# ariton_alexandru_fin.net
KiCad netlist of a schematic drawn in EAGLE
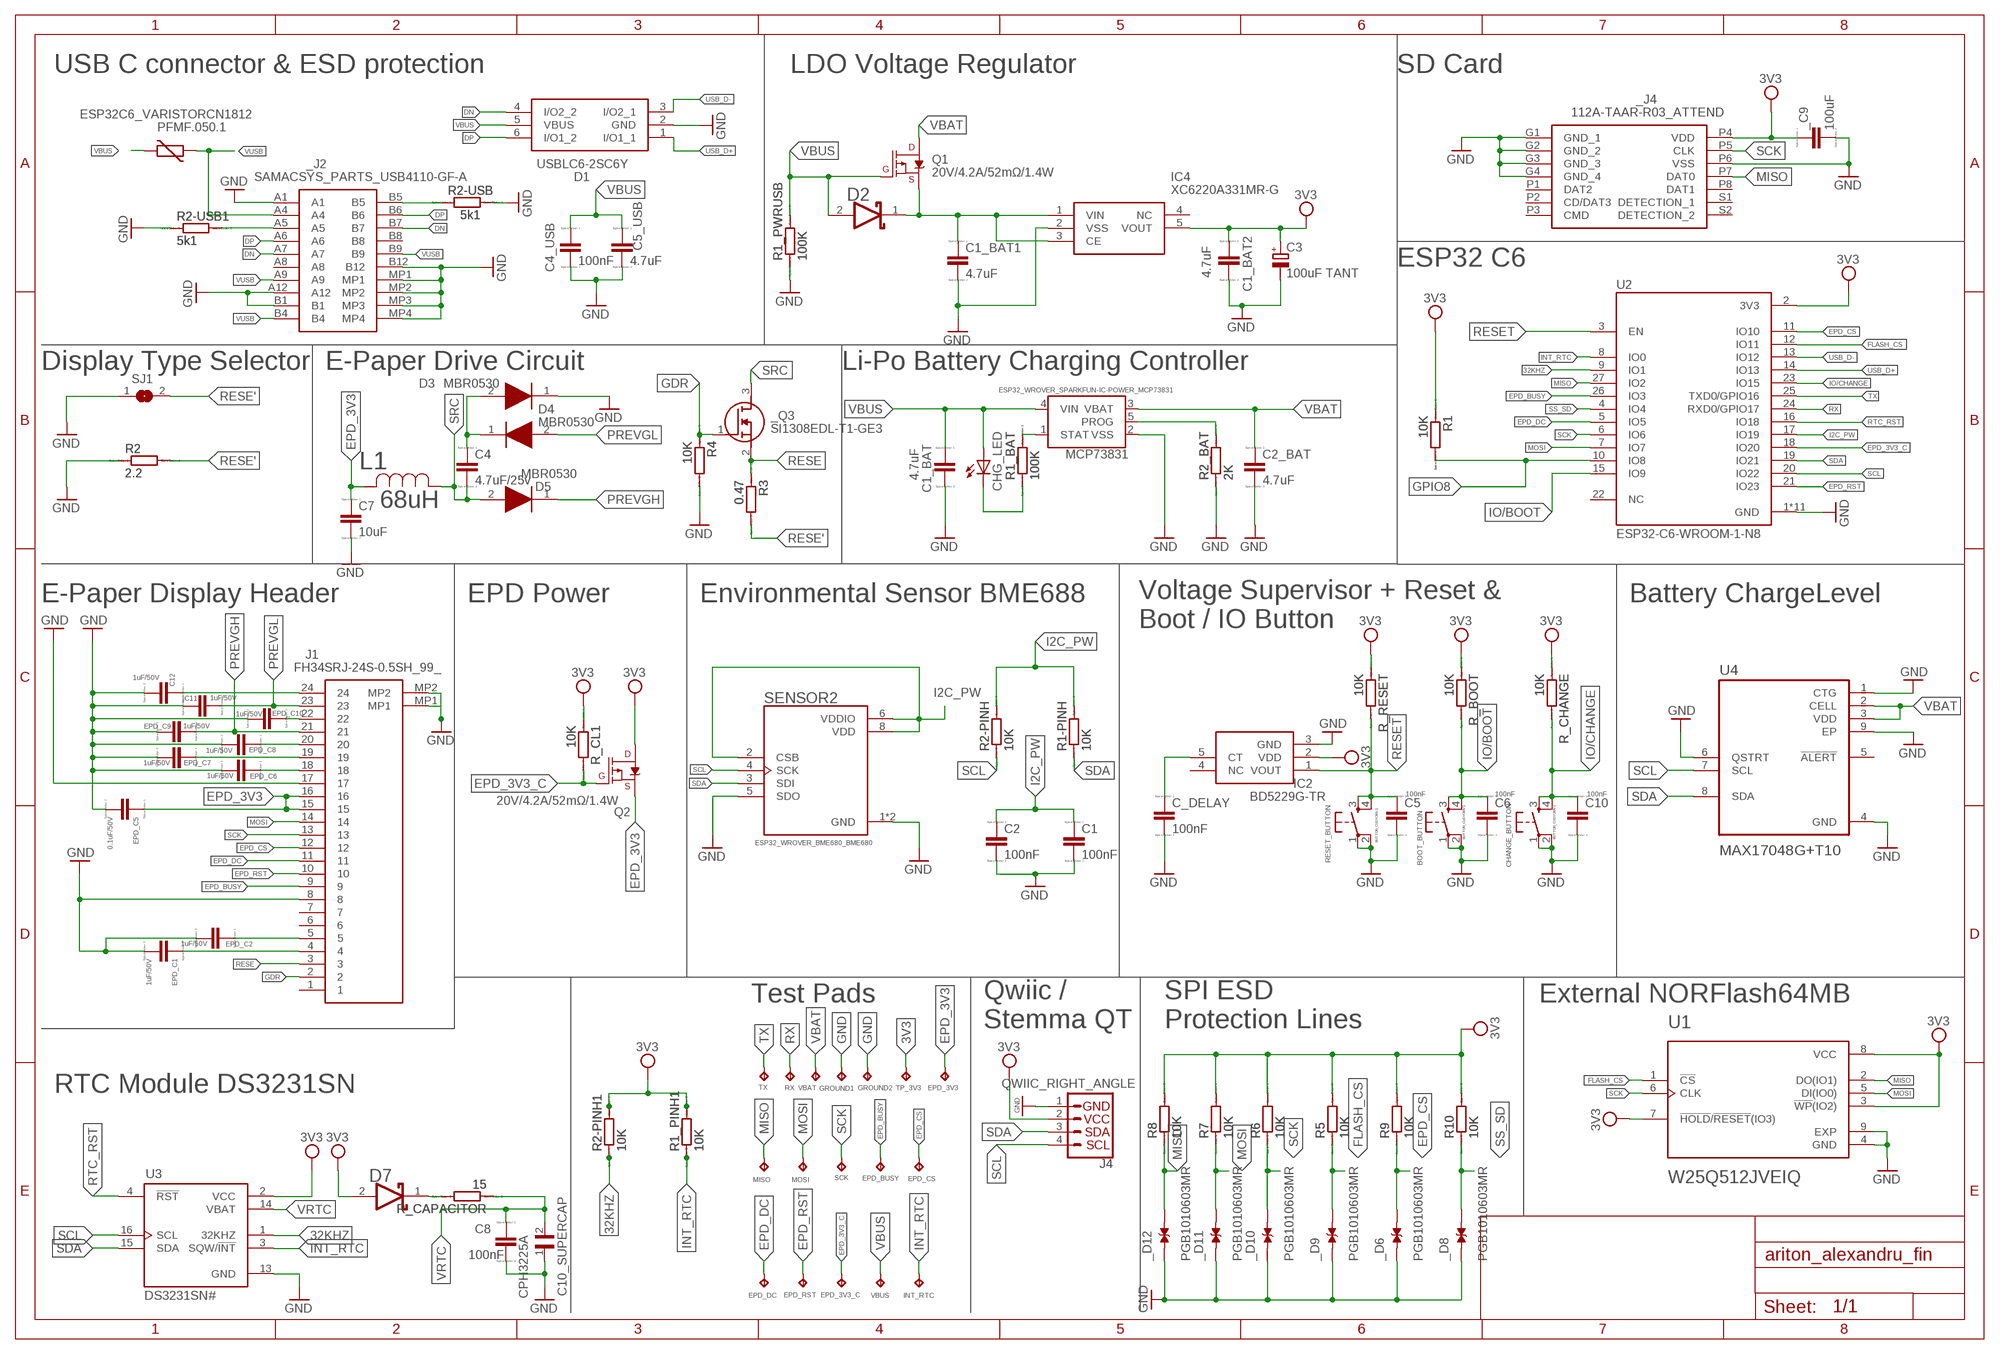
[diagram p0: schematic, sheet 1]

(export (version "E")
  (design (tool "Eeschema 10.0.6"))
  (components
    (comp (ref "BOOT_BUTTON")
      (value "BUTTON_CUSYOMV1")
      (footprint "eagle-import:MYBUTTON")
      (libsource (lib "eagle-import") (part "BUTTON_CUSYOMV1"))
    )
    (comp (ref "C1")
      (value "100nF")
      (footprint "eagle-import:EAGLE-LTSPICE_C0402")
      (libsource (lib "eagle-import") (part "EAGLE-LTSPICE_CC0402"))
    )
    (comp (ref "C1_BAT")
      (value "4.7uF")
      (footprint "eagle-import:EAGLE-LTSPICE_C0402")
      (libsource (lib "eagle-import") (part "EAGLE-LTSPICE_CC0402"))
    )
    (comp (ref "C1_BAT1")
      (value "4.7uF")
      (footprint "eagle-import:EAGLE-LTSPICE_C0402")
      (libsource (lib "eagle-import") (part "EAGLE-LTSPICE_CC0402"))
    )
    (comp (ref "C1_BAT2")
      (value "4.7uF")
      (footprint "eagle-import:EAGLE-LTSPICE_C0402")
      (libsource (lib "eagle-import") (part "EAGLE-LTSPICE_CC0402"))
    )
    (comp (ref "C2")
      (value "100nF")
      (footprint "eagle-import:EAGLE-LTSPICE_C0402")
      (libsource (lib "eagle-import") (part "EAGLE-LTSPICE_CC0402"))
    )
    (comp (ref "C2_BAT")
      (value "4.7uF")
      (footprint "eagle-import:EAGLE-LTSPICE_C0402")
      (libsource (lib "eagle-import") (part "EAGLE-LTSPICE_CC0402"))
    )
    (comp (ref "C3")
      (value "100uF TANT")
      (footprint "eagle-import:RCL_CT3528")
      (libsource (lib "eagle-import") (part "RCL_CPOL-EUCT3528"))
    )
    (comp (ref "C4")
      (value "4.7uF/25v")
      (footprint "eagle-import:EAGLE-LTSPICE_C0402")
      (libsource (lib "eagle-import") (part "EAGLE-LTSPICE_CC0402"))
    )
    (comp (ref "C4_USB")
      (value "100nF")
      (footprint "eagle-import:EAGLE-LTSPICE_C0402")
      (libsource (lib "eagle-import") (part "EAGLE-LTSPICE_CC0402"))
    )
    (comp (ref "C5")
      (value "100nF")
      (footprint "eagle-import:ESP32_WROVER_EAGLE-LTSPICE_C0402")
      (libsource (lib "eagle-import") (part "ESP32_WROVER_EAGLE-LTSPICE_CC0402"))
    )
    (comp (ref "C5_USB")
      (value "4.7uF")
      (footprint "eagle-import:EAGLE-LTSPICE_C0402")
      (libsource (lib "eagle-import") (part "EAGLE-LTSPICE_CC0402"))
    )
    (comp (ref "C6")
      (value "100nF")
      (footprint "eagle-import:ESP32_WROVER_EAGLE-LTSPICE_C0402")
      (libsource (lib "eagle-import") (part "ESP32_WROVER_EAGLE-LTSPICE_CC0402"))
    )
    (comp (ref "C7")
      (value "10uF")
      (footprint "eagle-import:EAGLE-LTSPICE_C0402")
      (libsource (lib "eagle-import") (part "EAGLE-LTSPICE_CC0402"))
    )
    (comp (ref "C8")
      (value "100nF")
      (footprint "eagle-import:EAGLE-LTSPICE_C0402")
      (libsource (lib "eagle-import") (part "EAGLE-LTSPICE_CC0402"))
    )
    (comp (ref "C10")
      (value "100nF")
      (footprint "eagle-import:ESP32_WROVER_EAGLE-LTSPICE_C0402")
      (libsource (lib "eagle-import") (part "ESP32_WROVER_EAGLE-LTSPICE_CC0402"))
    )
    (comp (ref "C10_SUPERCAP")
      (value "CPH3225A")
      (footprint "eagle-import:CAPCP3225X100N")
      (fields (field (name "MF") "Seiko Instruments"))
      (libsource (lib "eagle-import") (part "CPH3225A"))
    )
    (comp (ref "C11")
      (value "1uF/50V")
      (footprint "eagle-import:EAGLE-LTSPICE_C0402")
      (libsource (lib "eagle-import") (part "EAGLE-LTSPICE_CC0402"))
    )
    (comp (ref "C12")
      (value "1uF/50V")
      (footprint "eagle-import:EAGLE-LTSPICE_C0402")
      (libsource (lib "eagle-import") (part "EAGLE-LTSPICE_CC0402"))
    )
    (comp (ref "CHANGE_BUTTON")
      (value "BUTTON_CUSYOMV1")
      (footprint "eagle-import:MYBUTTON")
      (libsource (lib "eagle-import") (part "BUTTON_CUSYOMV1"))
    )
    (comp (ref "CHG_LED")
      (value "ADAFRUIT_LEDCHIP-LED0603")
      (footprint "eagle-import:ADAFRUIT_CHIP-LED0603")
      (libsource (lib "eagle-import") (part "ADAFRUIT_LEDCHIP-LED0603"))
    )
    (comp (ref "C_DELAY")
      (value "100nF")
      (footprint "eagle-import:ESP32_WROVER_EAGLE-LTSPICE_C0402")
      (libsource (lib "eagle-import") (part "ESP32_WROVER_EAGLE-LTSPICE_CC0402"))
    )
    (comp (ref "D1")
      (value "USBLC6-2SC6Y")
      (footprint "eagle-import:SOT95P280X145-6N")
      (fields (field (name "MF") "STMicroelectronics"))
      (libsource (lib "eagle-import") (part "USBLC6-2SC6Y"))
    )
    (comp (ref "D2")
      (value "ESP32_WROVER_AVX---SD0805S020S1R0_AVX_SD0805S020S1R0_0_0AVX_SD0805S020S1R0_0_0")
      (footprint "eagle-import:ESP32_WROVER_AVX---SD0805S020S1R0_AVX_SD0805S020S1R0_0")
      (fields
        (field (name "DIGIKEY_PART_NUMBER") "478-7800-1-ND")
        (field (name "MF") "AVX")
        (field (name "MOUSER_PART_NUMBER") "581-SD0805S020S1R0")
      )
      (libsource (lib "eagle-import") (part "ESP32_WROVER_AVX---SD0805S020S1R0_AVX_SD0805S020S1R0_0_0AVX_SD0805S020S1R0_0_0"))
    )
    (comp (ref "D3")
      (value "MBR0530")
      (footprint "eagle-import:SOD3716X135N")
      (fields (field (name "MF") "ON Semiconductor"))
      (libsource (lib "eagle-import") (part "MBR0530"))
    )
    (comp (ref "D4")
      (value "MBR0530")
      (footprint "eagle-import:SOD3716X135N")
      (fields (field (name "MF") "ON Semiconductor"))
      (libsource (lib "eagle-import") (part "MBR0530"))
    )
    (comp (ref "D5")
      (value "MBR0530")
      (footprint "eagle-import:SOD3716X135N")
      (fields (field (name "MF") "ON Semiconductor"))
      (libsource (lib "eagle-import") (part "MBR0530"))
    )
    (comp (ref "D7")
      (value "ESP32_WROVER_AVX---SD0805S020S1R0_AVX_SD0805S020S1R0_0_0AVX_SD0805S020S1R0_0_0")
      (footprint "eagle-import:ESP32_WROVER_AVX---SD0805S020S1R0_AVX_SD0805S020S1R0_0")
      (fields
        (field (name "DIGIKEY_PART_NUMBER") "478-7800-1-ND")
        (field (name "MF") "AVX")
        (field (name "MOUSER_PART_NUMBER") "581-SD0805S020S1R0")
      )
      (libsource (lib "eagle-import") (part "ESP32_WROVER_AVX---SD0805S020S1R0_AVX_SD0805S020S1R0_0_0AVX_SD0805S020S1R0_0_0"))
    )
    (comp (ref "EPD_3V3")
      (value "TPTP20R")
      (footprint "eagle-import:TP20R")
      (libsource (lib "eagle-import") (part "TPTP20R"))
    )
    (comp (ref "EPD_3V3_C")
      (value "TPTP20R")
      (footprint "eagle-import:TP20R")
      (libsource (lib "eagle-import") (part "TPTP20R"))
    )
    (comp (ref "EPD_BUSY")
      (value "TPTP20R")
      (footprint "eagle-import:TP20R")
      (libsource (lib "eagle-import") (part "TPTP20R"))
    )
    (comp (ref "EPD_C1")
      (value "1uF/50V")
      (footprint "eagle-import:EAGLE-LTSPICE_C0402")
      (libsource (lib "eagle-import") (part "EAGLE-LTSPICE_CC0402"))
    )
    (comp (ref "EPD_C2")
      (value "1uF/50V")
      (footprint "eagle-import:EAGLE-LTSPICE_C0402")
      (libsource (lib "eagle-import") (part "EAGLE-LTSPICE_CC0402"))
    )
    (comp (ref "EPD_C5")
      (value "0.1uF/50V")
      (footprint "eagle-import:EAGLE-LTSPICE_C0402")
      (libsource (lib "eagle-import") (part "EAGLE-LTSPICE_CC0402"))
    )
    (comp (ref "EPD_C6")
      (value "1uF/50V")
      (footprint "eagle-import:EAGLE-LTSPICE_C0402")
      (libsource (lib "eagle-import") (part "EAGLE-LTSPICE_CC0402"))
    )
    (comp (ref "EPD_C7")
      (value "1uF/50V")
      (footprint "eagle-import:EAGLE-LTSPICE_C0402")
      (libsource (lib "eagle-import") (part "EAGLE-LTSPICE_CC0402"))
    )
    (comp (ref "EPD_C8")
      (value "1uF/50V")
      (footprint "eagle-import:EAGLE-LTSPICE_C0402")
      (libsource (lib "eagle-import") (part "EAGLE-LTSPICE_CC0402"))
    )
    (comp (ref "EPD_C9")
      (value "1uF/50V")
      (footprint "eagle-import:EAGLE-LTSPICE_C0402")
      (libsource (lib "eagle-import") (part "EAGLE-LTSPICE_CC0402"))
    )
    (comp (ref "EPD_C10")
      (value "1uF/50V")
      (footprint "eagle-import:EAGLE-LTSPICE_C0402")
      (libsource (lib "eagle-import") (part "EAGLE-LTSPICE_CC0402"))
    )
    (comp (ref "EPD_CS")
      (value "TPTP20R")
      (footprint "eagle-import:TP20R")
      (libsource (lib "eagle-import") (part "TPTP20R"))
    )
    (comp (ref "EPD_DC")
      (value "TPTP20R")
      (footprint "eagle-import:TP20R")
      (libsource (lib "eagle-import") (part "TPTP20R"))
    )
    (comp (ref "EPD_RST")
      (value "TPTP20R")
      (footprint "eagle-import:TP20R")
      (libsource (lib "eagle-import") (part "TPTP20R"))
    )
    (comp (ref "GROUND1")
      (value "TPTP20R")
      (footprint "eagle-import:TP20R")
      (libsource (lib "eagle-import") (part "TPTP20R"))
    )
    (comp (ref "GROUND2")
      (value "TPTP20R")
      (footprint "eagle-import:TP20R")
      (libsource (lib "eagle-import") (part "TPTP20R"))
    )
    (comp (ref "IC2")
      (value "BD5229G-TR")
      (footprint "eagle-import:SOT95P280X125-5N")
      (fields (field (name "MOUSER_PART_NUMBER") "755-BD5229G-TR"))
      (libsource (lib "eagle-import") (part "BD5229G-TR"))
    )
    (comp (ref "IC4")
      (value "XC6220A331MR-G")
      (footprint "eagle-import:SOT95P280X120-5N")
      (fields (field (name "MOUSER_PART_NUMBER") "865-XC6220A331MR-G"))
      (libsource (lib "eagle-import") (part "XC6220A331MR-G"))
    )
    (comp (ref "INT_RTC")
      (value "TPTP20R")
      (footprint "eagle-import:TP20R")
      (libsource (lib "eagle-import") (part "TPTP20R"))
    )
    (comp (ref "J1")
      (value "FH34SRJ-24S-0.5SH_99_")
      (footprint "eagle-import:FH34SRJ24S05SH99")
      (fields
        (field (name "MANUFACTURER_PART_NUMBER") "FH34SRJ-24S-0.5SH(99)")
        (field (name "MOUSER_PART_NUMBER") "798-FH34SRJ24S05SH99")
      )
      (libsource (lib "eagle-import") (part "FH34SRJ-24S-0.5SH_99_"))
    )
    (comp (ref "J4")
      (value "QWIIC_RIGHT_ANGLE")
      (footprint "eagle-import:JST04_1MM_RA")
      (libsource (lib "eagle-import") (part "QWIIC_CONNECTORJS-1MM"))
    )
    (comp (ref "L1")
      (value "68uH")
      (footprint "eagle-import:IND_4828-WE-TPC_WRE")
      (fields
        (field (name "MANUFACTURER_PART_NUMBER") "744043680")
        (field (name "COPYRIGHT") "Copyright (C) 2024 Ultra Librarian. All rights reserved.")
      )
      (libsource (lib "eagle-import") (part "744043680IND_4828-WE-TPC_WRE"))
    )
    (comp (ref "MCP73831")
      (value "ESP32_WROVER_SPARKFUN-IC-POWER_MCP73831")
      (footprint "eagle-import:ESP32_WROVER_SPARKFUN-IC-POWER_SOT23-5")
      (libsource (lib "eagle-import") (part "ESP32_WROVER_SPARKFUN-IC-POWER_MCP73831"))
    )
    (comp (ref "MISO")
      (value "TPTP20R")
      (footprint "eagle-import:TP20R")
      (libsource (lib "eagle-import") (part "TPTP20R"))
    )
    (comp (ref "MOSI")
      (value "TPTP20R")
      (footprint "eagle-import:TP20R")
      (libsource (lib "eagle-import") (part "TPTP20R"))
    )
    (comp (ref "PFMF.050.1")
      (value "ESP32C6_VARISTORCN1812")
      (footprint "eagle-import:ESP32C6_VARISTOR_CT_CN1812")
      (libsource (lib "eagle-import") (part "ESP32C6_VARISTORCN1812"))
    )
    (comp (ref "Q1")
      (value "20V/4.2A/52mΩ/1.4W")
      (footprint "eagle-import:ESP32_WROVER_SPARKFUN-DISCRETESEMI_SOT23-3")
      (libsource (lib "eagle-import") (part "ESP32_WROVER_SPARKFUN-DISCRETESEMI_MOSFET_PCH-DMG2305UX-7"))
    )
    (comp (ref "Q2")
      (value "20V/4.2A/52mΩ/1.4W")
      (footprint "eagle-import:ESP32_WROVER_SPARKFUN-DISCRETESEMI_SOT23-3")
      (libsource (lib "eagle-import") (part "ESP32_WROVER_SPARKFUN-DISCRETESEMI_MOSFET_PCH-DMG2305UX-7"))
    )
    (comp (ref "R1")
      (value "10K")
      (footprint "eagle-import:ESP32_WROVER_EAGLE-LTSPICE_R0402")
      (libsource (lib "eagle-import") (part "ESP32_WROVER_EAGLE-LTSPICE_RR0402"))
    )
    (comp (ref "R1-PINH")
      (value "10K")
      (footprint "eagle-import:ESP32_WROVER_EAGLE-LTSPICE_R0402")
      (libsource (lib "eagle-import") (part "ESP32_WROVER_EAGLE-LTSPICE_RR0402"))
    )
    (comp (ref "R1_BAT")
      (value "100K")
      (footprint "eagle-import:ESP32_WROVER_EAGLE-LTSPICE_R0402")
      (libsource (lib "eagle-import") (part "ESP32_WROVER_EAGLE-LTSPICE_RR0402"))
    )
    (comp (ref "R1_PINH1")
      (value "10K")
      (footprint "eagle-import:ESP32_WROVER_EAGLE-LTSPICE_R0402")
      (libsource (lib "eagle-import") (part "ESP32_WROVER_EAGLE-LTSPICE_RR0402"))
    )
    (comp (ref "R1_PWRUSB")
      (value "100K")
      (footprint "eagle-import:ESP32_WROVER_EAGLE-LTSPICE_R0402")
      (libsource (lib "eagle-import") (part "ESP32_WROVER_EAGLE-LTSPICE_RR0402"))
    )
    (comp (ref "R2")
      (value "2.2")
      (footprint "eagle-import:ESP32_WROVER_EAGLE-LTSPICE_R0402")
      (libsource (lib "eagle-import") (part "ESP32_WROVER_EAGLE-LTSPICE_RR0402"))
    )
    (comp (ref "R2-PINH")
      (value "10K")
      (footprint "eagle-import:ESP32_WROVER_EAGLE-LTSPICE_R0402")
      (libsource (lib "eagle-import") (part "ESP32_WROVER_EAGLE-LTSPICE_RR0402"))
    )
    (comp (ref "R2-PINH1")
      (value "10K")
      (footprint "eagle-import:ESP32_WROVER_EAGLE-LTSPICE_R0402")
      (libsource (lib "eagle-import") (part "ESP32_WROVER_EAGLE-LTSPICE_RR0402"))
    )
    (comp (ref "R2-USB")
      (value "5k1")
      (footprint "eagle-import:ESP32_WROVER_EAGLE-LTSPICE_R0402")
      (libsource (lib "eagle-import") (part "ESP32_WROVER_EAGLE-LTSPICE_RR0402"))
    )
    (comp (ref "R2-USB1")
      (value "5k1")
      (footprint "eagle-import:ESP32_WROVER_EAGLE-LTSPICE_R0402")
      (libsource (lib "eagle-import") (part "ESP32_WROVER_EAGLE-LTSPICE_RR0402"))
    )
    (comp (ref "R2_BAT")
      (value "2K")
      (footprint "eagle-import:ESP32_WROVER_EAGLE-LTSPICE_R0402")
      (libsource (lib "eagle-import") (part "ESP32_WROVER_EAGLE-LTSPICE_RR0402"))
    )
    (comp (ref "R3")
      (value "0.47")
      (footprint "eagle-import:ESP32_WROVER_EAGLE-LTSPICE_R0402")
      (libsource (lib "eagle-import") (part "ESP32_WROVER_EAGLE-LTSPICE_RR0402"))
    )
    (comp (ref "R4")
      (value "10K")
      (footprint "eagle-import:ESP32_WROVER_EAGLE-LTSPICE_R0402")
      (libsource (lib "eagle-import") (part "ESP32_WROVER_EAGLE-LTSPICE_RR0402"))
    )
    (comp (ref "R5")
      (value "10K")
      (footprint "eagle-import:ESP32_WROVER_EAGLE-LTSPICE_R0402")
      (libsource (lib "eagle-import") (part "ESP32_WROVER_EAGLE-LTSPICE_RR0402"))
    )
    (comp (ref "R6")
      (value "10K")
      (footprint "eagle-import:ESP32_WROVER_EAGLE-LTSPICE_R0402")
      (libsource (lib "eagle-import") (part "ESP32_WROVER_EAGLE-LTSPICE_RR0402"))
    )
    (comp (ref "R7")
      (value "10K")
      (footprint "eagle-import:ESP32_WROVER_EAGLE-LTSPICE_R0402")
      (libsource (lib "eagle-import") (part "ESP32_WROVER_EAGLE-LTSPICE_RR0402"))
    )
    (comp (ref "R8")
      (value "10K")
      (footprint "eagle-import:ESP32_WROVER_EAGLE-LTSPICE_R0402")
      (libsource (lib "eagle-import") (part "ESP32_WROVER_EAGLE-LTSPICE_RR0402"))
    )
    (comp (ref "R9")
      (value "10K")
      (footprint "eagle-import:ESP32_WROVER_EAGLE-LTSPICE_R0402")
      (libsource (lib "eagle-import") (part "ESP32_WROVER_EAGLE-LTSPICE_RR0402"))
    )
    (comp (ref "R10")
      (value "10K")
      (footprint "eagle-import:ESP32_WROVER_EAGLE-LTSPICE_R0402")
      (libsource (lib "eagle-import") (part "ESP32_WROVER_EAGLE-LTSPICE_RR0402"))
    )
    (comp (ref "RESET_BUTTON")
      (value "BUTTON_CUSYOMV1")
      (footprint "eagle-import:MYBUTTON")
      (libsource (lib "eagle-import") (part "BUTTON_CUSYOMV1"))
    )
    (comp (ref "RX")
      (value "TPTP20R")
      (footprint "eagle-import:TP20R")
      (libsource (lib "eagle-import") (part "TPTP20R"))
    )
    (comp (ref "R_BOOT")
      (value "10K")
      (footprint "eagle-import:ESP32_WROVER_EAGLE-LTSPICE_R0402")
      (libsource (lib "eagle-import") (part "ESP32_WROVER_EAGLE-LTSPICE_RR0402"))
    )
    (comp (ref "R_CAPACITOR")
      (value "15")
      (footprint "eagle-import:ESP32_WROVER_EAGLE-LTSPICE_R0402")
      (libsource (lib "eagle-import") (part "ESP32_WROVER_EAGLE-LTSPICE_RR0402"))
    )
    (comp (ref "R_CHANGE")
      (value "10K")
      (footprint "eagle-import:ESP32_WROVER_EAGLE-LTSPICE_R0402")
      (libsource (lib "eagle-import") (part "ESP32_WROVER_EAGLE-LTSPICE_RR0402"))
    )
    (comp (ref "R_CL1")
      (value "10K")
      (footprint "eagle-import:ESP32_WROVER_EAGLE-LTSPICE_R0402")
      (libsource (lib "eagle-import") (part "ESP32_WROVER_EAGLE-LTSPICE_RR0402"))
    )
    (comp (ref "R_RESET")
      (value "10K")
      (footprint "eagle-import:ESP32_WROVER_EAGLE-LTSPICE_R0402")
      (libsource (lib "eagle-import") (part "ESP32_WROVER_EAGLE-LTSPICE_RR0402"))
    )
    (comp (ref "SCK")
      (value "TPTP20R")
      (footprint "eagle-import:TP20R")
      (libsource (lib "eagle-import") (part "TPTP20R"))
    )
    (comp (ref "SENSOR2")
      (value "ESP32_WROVER_BME680_BME680")
      (footprint "eagle-import:ESP32_WROVER_BME680_PSON80P300X300X100-8N")
      (fields (field (name "MF") "Bosch Sensortec") (field (name "MP") "BME680"))
      (libsource (lib "eagle-import") (part "ESP32_WROVER_BME680_BME680"))
    )
    (comp (ref "SJ1") (value "SJ") (footprint "eagle-import:SJ") (libsource (lib "eagle-import") (part "SJ")))
    (comp (ref "TP_3V3")
      (value "TPTP20R")
      (footprint "eagle-import:TP20R")
      (libsource (lib "eagle-import") (part "TPTP20R"))
    )
    (comp (ref "TX")
      (value "TPTP20R")
      (footprint "eagle-import:TP20R")
      (libsource (lib "eagle-import") (part "TPTP20R"))
    )
    (comp (ref "U1")
      (value "W25Q512JVEIQ")
      (footprint "eagle-import:SON127P600X800X80-9N")
      (fields (field (name "MF") "Winbond Electronics"))
      (libsource (lib "eagle-import") (part "W25Q512JVEIQ"))
    )
    (comp (ref "U2")
      (value "ESP32-C6-WROOM-1-N8")
      (footprint "eagle-import:XCVR_ESP32-C6-WROOM-1-N8")
      (fields (field (name "MF") "Espressif Systems"))
      (libsource (lib "eagle-import") (part "ESP32-C6-WROOM-1-N8"))
    )
    (comp (ref "U3")
      (value "DS3231SN#")
      (footprint "eagle-import:SOIC127P1032X265-16N")
      (fields (field (name "MF") "Analog Devices"))
      (libsource (lib "eagle-import") (part "DS3231SN#"))
    )
    (comp (ref "U4")
      (value "MAX17048G+T10")
      (footprint "eagle-import:SON50P200X200X80-9N")
      (fields (field (name "MF") "Analog Devices"))
      (libsource (lib "eagle-import") (part "MAX17048G+T10"))
    )
    (comp (ref "VBAT")
      (value "TPTP20R")
      (footprint "eagle-import:TP20R")
      (libsource (lib "eagle-import") (part "TPTP20R"))
    )
    (comp (ref "VBUS")
      (value "TPTP20R")
      (footprint "eagle-import:TP20R")
      (libsource (lib "eagle-import") (part "TPTP20R"))
    )
    (comp (ref "_C9")
      (value "100uF")
      (footprint "eagle-import:EAGLE-LTSPICE_C0402")
      (libsource (lib "eagle-import") (part "EAGLE-LTSPICE_CC0402"))
    )
    (comp (ref "_D6")
      (value "PGB1010603MR")
      (footprint "eagle-import:DIOC1608X36N")
      (fields (field (name "MF") "Littelfuse Inc."))
      (libsource (lib "eagle-import") (part "PGB1010603MR"))
    )
    (comp (ref "_D8")
      (value "PGB1010603MR")
      (footprint "eagle-import:DIOC1608X36N")
      (fields (field (name "MF") "Littelfuse Inc."))
      (libsource (lib "eagle-import") (part "PGB1010603MR"))
    )
    (comp (ref "_D9")
      (value "PGB1010603MR")
      (footprint "eagle-import:DIOC1608X36N")
      (fields (field (name "MF") "Littelfuse Inc."))
      (libsource (lib "eagle-import") (part "PGB1010603MR"))
    )
    (comp (ref "_D10")
      (value "PGB1010603MR")
      (footprint "eagle-import:DIOC1608X36N")
      (fields (field (name "MF") "Littelfuse Inc."))
      (libsource (lib "eagle-import") (part "PGB1010603MR"))
    )
    (comp (ref "_D11")
      (value "PGB1010603MR")
      (footprint "eagle-import:DIOC1608X36N")
      (fields (field (name "MF") "Littelfuse Inc."))
      (libsource (lib "eagle-import") (part "PGB1010603MR"))
    )
    (comp (ref "_D12")
      (value "PGB1010603MR")
      (footprint "eagle-import:DIOC1608X36N")
      (fields (field (name "MF") "Littelfuse Inc."))
      (libsource (lib "eagle-import") (part "PGB1010603MR"))
    )
    (comp (ref "_J2")
      (value "SAMACSYS_PARTS_USB4110-GF-A")
      (footprint "eagle-import:SAMACSYS_PARTS_USB4110GFA")
      (fields
        (field (name "MANUFACTURER_PART_NUMBER") "USB4110-GF-A")
        (field (name "MOUSER_PART_NUMBER") "640-USB4110-GF-A")
      )
      (libsource (lib "eagle-import") (part "SAMACSYS_PARTS_USB4110-GF-A"))
    )
    (comp (ref "_J4")
      (value "112A-TAAR-R03_ATTEND")
      (footprint "eagle-import:112ATAARR03ATTEND")
      (fields (field (name "MANUFACTURER_PART_NUMBER") "112A-TAAR-R03 ATTEND"))
      (libsource (lib "eagle-import") (part "112A-TAAR-R03_ATTEND"))
    )
    (comp (ref "_Q3")
      (value "SI1308EDL-T1-GE3")
      (footprint "eagle-import:SOT65P210X110-3N")
      (fields (field (name "MF") "Vishay Siliconix"))
      (libsource (lib "eagle-import") (part "SI1308EDL-T1-GE3"))
    )
  )
  (nets
    (net (code "1") (name "3V3") (class "Default")
      (node (ref "C1_BAT2") (pin "1") (pinfunction "1_1") (pintype "passive"))
      (node (ref "C3") (pin "+") (pinfunction "+_+") (pintype "passive"))
      (node (ref "D7") (pin "2") (pinfunction "ANODE_2") (pintype "bidirectional"))
      (node (ref "IC2") (pin "2") (pinfunction "VDD_2") (pintype "bidirectional"))
      (node (ref "IC4") (pin "5") (pinfunction "VOUT_5") (pintype "bidirectional"))
      (node (ref "J4") (pin "2") (pinfunction "2_2") (pintype "power_in"))
      (node (ref "Q2") (pin "3") (pinfunction "D_3") (pintype "bidirectional"))
      (node (ref "R1") (pin "1") (pinfunction "1_1") (pintype "passive"))
      (node (ref "R10") (pin "2") (pinfunction "2_2") (pintype "passive"))
      (node (ref "R1_PINH1") (pin "2") (pinfunction "2_2") (pintype "passive"))
      (node (ref "R2-PINH1") (pin "2") (pinfunction "2_2") (pintype "passive"))
      (node (ref "R5") (pin "2") (pinfunction "2_2") (pintype "passive"))
      (node (ref "R6") (pin "2") (pinfunction "2_2") (pintype "passive"))
      (node (ref "R7") (pin "2") (pinfunction "2_2") (pintype "passive"))
      (node (ref "R8") (pin "2") (pinfunction "2_2") (pintype "passive"))
      (node (ref "R9") (pin "2") (pinfunction "2_2") (pintype "passive"))
      (node (ref "R_BOOT") (pin "1") (pinfunction "1_1") (pintype "passive"))
      (node (ref "R_CHANGE") (pin "1") (pinfunction "1_1") (pintype "passive"))
      (node (ref "R_CL1") (pin "1") (pinfunction "1_1") (pintype "passive"))
      (node (ref "R_RESET") (pin "1") (pinfunction "1_1") (pintype "passive"))
      (node (ref "TP_3V3") (pin "TP") (pinfunction "TP_TP") (pintype "input"))
      (node (ref "U1") (pin "3") (pinfunction "~{WP}(IO2)_3") (pintype "bidirectional"))
      (node (ref "U1") (pin "7") (pinfunction "~{HOLD}/~{RESET}(IO3)_7") (pintype "bidirectional"))
      (node (ref "U1") (pin "8") (pinfunction "VCC_8") (pintype "power_in"))
      (node (ref "U2") (pin "2") (pinfunction "3V3_2") (pintype "power_in"))
      (node (ref "U3") (pin "2") (pinfunction "VCC_2") (pintype "power_in"))
      (node (ref "_C9") (pin "1") (pinfunction "1_1") (pintype "passive"))
      (node (ref "_J4") (pin "P4") (pinfunction "VDD_P4") (pintype "bidirectional"))
    )
    (net (code "2") (name "32KHZ") (class "Default")
      (node (ref "R2-PINH1") (pin "1") (pinfunction "1_1") (pintype "passive"))
      (node (ref "U2") (pin "9") (pinfunction "IO1_9") (pintype "bidirectional"))
      (node (ref "U3") (pin "1") (pinfunction "32KHZ_1") (pintype "output"))
    )
    (net (code "3") (name "DN") (class "Default")
      (node (ref "D1") (pin "4") (pinfunction "I/O2_2_4") (pintype "bidirectional"))
      (node (ref "_J2") (pin "A7") (pinfunction "A7_A7") (pintype "bidirectional"))
      (node (ref "_J2") (pin "B7") (pinfunction "B7_B7") (pintype "bidirectional"))
    )
    (net (code "4") (name "DP") (class "Default")
      (node (ref "D1") (pin "6") (pinfunction "I/O1_2_6") (pintype "bidirectional"))
      (node (ref "_J2") (pin "A6") (pinfunction "A6_A6") (pintype "bidirectional"))
      (node (ref "_J2") (pin "B6") (pinfunction "B6_B6") (pintype "bidirectional"))
    )
    (net (code "5") (name "EPD_3V3") (class "Default")
      (node (ref "C7") (pin "1") (pinfunction "1_1") (pintype "passive"))
      (node (ref "EPD_3V3") (pin "TP") (pinfunction "TP_TP") (pintype "input"))
      (node (ref "EPD_C5") (pin "1") (pinfunction "1_1") (pintype "passive"))
      (node (ref "J1") (pin "15") (pinfunction "15_15") (pintype "bidirectional"))
      (node (ref "J1") (pin "16") (pinfunction "16_16") (pintype "bidirectional"))
      (node (ref "L1") (pin "2") (pinfunction "2_2") (pintype "passive"))
      (node (ref "Q2") (pin "2") (pinfunction "S_2") (pintype "bidirectional"))
    )
    (net (code "6") (name "EPD_3V3_C") (class "Default")
      (node (ref "EPD_3V3_C") (pin "TP") (pinfunction "TP_TP") (pintype "input"))
      (node (ref "Q2") (pin "1") (pinfunction "G_1") (pintype "bidirectional"))
      (node (ref "R_CL1") (pin "2") (pinfunction "2_2") (pintype "passive"))
      (node (ref "U2") (pin "18") (pinfunction "IO20_18") (pintype "bidirectional"))
    )
    (net (code "7") (name "EPD_BUSY") (class "Default")
      (node (ref "EPD_BUSY") (pin "TP") (pinfunction "TP_TP") (pintype "input"))
      (node (ref "J1") (pin "9") (pinfunction "9_9") (pintype "bidirectional"))
      (node (ref "U2") (pin "26") (pinfunction "IO3_26") (pintype "bidirectional"))
    )
    (net (code "8") (name "EPD_CS") (class "Default")
      (node (ref "EPD_CS") (pin "TP") (pinfunction "TP_TP") (pintype "input"))
      (node (ref "J1") (pin "12") (pinfunction "12_12") (pintype "bidirectional"))
      (node (ref "R9") (pin "1") (pinfunction "1_1") (pintype "passive"))
      (node (ref "U2") (pin "11") (pinfunction "IO10_11") (pintype "bidirectional"))
      (node (ref "_D6") (pin "2") (pinfunction "2_2") (pintype "passive"))
    )
    (net (code "9") (name "EPD_DC") (class "Default")
      (node (ref "EPD_DC") (pin "TP") (pinfunction "TP_TP") (pintype "input"))
      (node (ref "J1") (pin "11") (pinfunction "11_11") (pintype "bidirectional"))
      (node (ref "U2") (pin "5") (pinfunction "IO5_5") (pintype "bidirectional"))
    )
    (net (code "10") (name "EPD_RST") (class "Default")
      (node (ref "EPD_RST") (pin "TP") (pinfunction "TP_TP") (pintype "input"))
      (node (ref "J1") (pin "10") (pinfunction "10_10") (pintype "bidirectional"))
      (node (ref "U2") (pin "21") (pinfunction "IO23_21") (pintype "bidirectional"))
    )
    (net (code "11") (name "FLASH_CS") (class "Default")
      (node (ref "R5") (pin "1") (pinfunction "1_1") (pintype "passive"))
      (node (ref "U1") (pin "1") (pinfunction "~{CS}_1") (pintype "input"))
      (node (ref "U2") (pin "12") (pinfunction "IO11_12") (pintype "bidirectional"))
      (node (ref "_D9") (pin "2") (pinfunction "2_2") (pintype "passive"))
    )
    (net (code "12") (name "GDR") (class "Default")
      (node (ref "J1") (pin "2") (pinfunction "2_2") (pintype "bidirectional"))
      (node (ref "R4") (pin "1") (pinfunction "1_1") (pintype "passive"))
      (node (ref "_Q3") (pin "1") (pinfunction "G_1") (pintype "bidirectional"))
    )
    (net (code "13") (name "GND") (class "Default")
      (node (ref "BOOT_BUTTON") (pin "1") (pinfunction "1_1") (pintype "passive"))
      (node (ref "BOOT_BUTTON") (pin "2") (pinfunction "2_2") (pintype "passive"))
      (node (ref "C1") (pin "2") (pinfunction "2_2") (pintype "passive"))
      (node (ref "C10") (pin "2") (pinfunction "2_2") (pintype "passive"))
      (node (ref "C10_SUPERCAP") (pin "1") (pinfunction "1_1") (pintype "passive"))
      (node (ref "C11") (pin "2") (pinfunction "2_2") (pintype "passive"))
      (node (ref "C12") (pin "2") (pinfunction "2_2") (pintype "passive"))
      (node (ref "C1_BAT") (pin "2") (pinfunction "2_2") (pintype "passive"))
      (node (ref "C1_BAT1") (pin "2") (pinfunction "2_2") (pintype "passive"))
      (node (ref "C1_BAT2") (pin "2") (pinfunction "2_2") (pintype "passive"))
      (node (ref "C2") (pin "2") (pinfunction "2_2") (pintype "passive"))
      (node (ref "C2_BAT") (pin "2") (pinfunction "2_2") (pintype "passive"))
      (node (ref "C3") (pin "-") (pinfunction "-_-") (pintype "passive"))
      (node (ref "C4_USB") (pin "2") (pinfunction "2_2") (pintype "passive"))
      (node (ref "C5") (pin "2") (pinfunction "2_2") (pintype "passive"))
      (node (ref "C5_USB") (pin "2") (pinfunction "2_2") (pintype "passive"))
      (node (ref "C6") (pin "2") (pinfunction "2_2") (pintype "passive"))
      (node (ref "C7") (pin "2") (pinfunction "2_2") (pintype "passive"))
      (node (ref "C8") (pin "2") (pinfunction "2_2") (pintype "passive"))
      (node (ref "CHANGE_BUTTON") (pin "1") (pinfunction "1_1") (pintype "passive"))
      (node (ref "CHANGE_BUTTON") (pin "2") (pinfunction "2_2") (pintype "passive"))
      (node (ref "C_DELAY") (pin "2") (pinfunction "2_2") (pintype "passive"))
      (node (ref "D1") (pin "2") (pinfunction "GND_2") (pintype "bidirectional"))
      (node (ref "D3") (pin "1") (pinfunction "K_1") (pintype "bidirectional"))
      (node (ref "EPD_C1") (pin "2") (pinfunction "2_2") (pintype "passive"))
      (node (ref "EPD_C10") (pin "2") (pinfunction "2_2") (pintype "passive"))
      (node (ref "EPD_C2") (pin "2") (pinfunction "2_2") (pintype "passive"))
      (node (ref "EPD_C5") (pin "2") (pinfunction "2_2") (pintype "passive"))
      (node (ref "EPD_C6") (pin "2") (pinfunction "2_2") (pintype "passive"))
      (node (ref "EPD_C7") (pin "2") (pinfunction "2_2") (pintype "passive"))
      (node (ref "EPD_C8") (pin "2") (pinfunction "2_2") (pintype "passive"))
      (node (ref "EPD_C9") (pin "2") (pinfunction "2_2") (pintype "passive"))
      (node (ref "GROUND1") (pin "TP") (pinfunction "TP_TP") (pintype "input"))
      (node (ref "GROUND2") (pin "TP") (pinfunction "TP_TP") (pintype "input"))
      (node (ref "IC2") (pin "3") (pinfunction "GND_3") (pintype "bidirectional"))
      (node (ref "IC4") (pin "2") (pinfunction "VSS_2") (pintype "bidirectional"))
      (node (ref "J1") (pin "17") (pinfunction "17_17") (pintype "bidirectional"))
      (node (ref "J1") (pin "8") (pinfunction "8_8") (pintype "bidirectional"))
      (node (ref "J1") (pin "MP1") (pinfunction "MP1_MP1") (pintype "bidirectional"))
      (node (ref "J1") (pin "MP2") (pinfunction "MP2_MP2") (pintype "bidirectional"))
      (node (ref "J4") (pin "1") (pinfunction "1_1") (pintype "power_in"))
      (node (ref "MCP73831") (pin "2") (pinfunction "VSS_2") (pintype "power_in"))
      (node (ref "R1_PWRUSB") (pin "1") (pinfunction "1_1") (pintype "passive"))
      (node (ref "R2") (pin "1") (pinfunction "1_1") (pintype "passive"))
      (node (ref "R2-USB") (pin "2") (pinfunction "2_2") (pintype "passive"))
      (node (ref "R2-USB1") (pin "1") (pinfunction "1_1") (pintype "passive"))
      (node (ref "R2_BAT") (pin "1") (pinfunction "1_1") (pintype "passive"))
      (node (ref "R4") (pin "2") (pinfunction "2_2") (pintype "passive"))
      (node (ref "RESET_BUTTON") (pin "1") (pinfunction "1_1") (pintype "passive"))
      (node (ref "RESET_BUTTON") (pin "2") (pinfunction "2_2") (pintype "passive"))
      (node (ref "SENSOR2") (pin "1") (pinfunction "GND_1") (pintype "power_in"))
      (node (ref "SENSOR2") (pin "5") (pinfunction "SDO_5") (pintype "bidirectional"))
      (node (ref "SENSOR2") (pin "7") (pinfunction "GND_7") (pintype "power_in"))
      (node (ref "SJ1") (pin "1") (pinfunction "1_1") (pintype "passive"))
      (node (ref "U1") (pin "4") (pinfunction "GND_4") (pintype "power_in"))
      (node (ref "U1") (pin "9") (pinfunction "EXP_9") (pintype "passive"))
      (node (ref "U2") (pin "1") (pinfunction "GND_1") (pintype "power_in"))
      (node (ref "U2") (pin "28") (pinfunction "GND_28") (pintype "power_in"))
      (node (ref "U2") (pin "29_1") (pinfunction "GND_29_1") (pintype "power_in"))
      (node (ref "U2") (pin "29_2") (pinfunction "GND_29_2") (pintype "power_in"))
      (node (ref "U2") (pin "29_3") (pinfunction "GND_29_3") (pintype "power_in"))
      (node (ref "U2") (pin "29_4") (pinfunction "GND_29_4") (pintype "power_in"))
      (node (ref "U2") (pin "29_5") (pinfunction "GND_29_5") (pintype "power_in"))
      (node (ref "U2") (pin "29_6") (pinfunction "GND_29_6") (pintype "power_in"))
      (node (ref "U2") (pin "29_7") (pinfunction "GND_29_7") (pintype "power_in"))
      (node (ref "U2") (pin "29_8") (pinfunction "GND_29_8") (pintype "power_in"))
      (node (ref "U2") (pin "29_9") (pinfunction "GND_29_9") (pintype "power_in"))
      (node (ref "U3") (pin "13") (pinfunction "GND_13") (pintype "power_in"))
      (node (ref "U4") (pin "1") (pinfunction "CTG_1") (pintype "power_in"))
      (node (ref "U4") (pin "4") (pinfunction "GND_4") (pintype "power_in"))
      (node (ref "U4") (pin "6") (pinfunction "QSTRT_6") (pintype "input"))
      (node (ref "U4") (pin "9") (pinfunction "EP_9") (pintype "power_in"))
      (node (ref "_C9") (pin "2") (pinfunction "2_2") (pintype "passive"))
      (node (ref "_D10") (pin "1") (pinfunction "1_1") (pintype "passive"))
      (node (ref "_D11") (pin "1") (pinfunction "1_1") (pintype "passive"))
      (node (ref "_D12") (pin "1") (pinfunction "1_1") (pintype "passive"))
      (node (ref "_D6") (pin "1") (pinfunction "1_1") (pintype "passive"))
      (node (ref "_D8") (pin "1") (pinfunction "1_1") (pintype "passive"))
      (node (ref "_D9") (pin "1") (pinfunction "1_1") (pintype "passive"))
      (node (ref "_J2") (pin "A1") (pinfunction "A1_A1") (pintype "bidirectional"))
      (node (ref "_J2") (pin "A12") (pinfunction "A12_A12") (pintype "bidirectional"))
      (node (ref "_J2") (pin "B1") (pinfunction "B1_B1") (pintype "bidirectional"))
      (node (ref "_J2") (pin "B12") (pinfunction "B12_B12") (pintype "bidirectional"))
      (node (ref "_J2") (pin "MP1") (pinfunction "MP1_MP1") (pintype "bidirectional"))
      (node (ref "_J2") (pin "MP2") (pinfunction "MP2_MP2") (pintype "bidirectional"))
      (node (ref "_J2") (pin "MP3") (pinfunction "MP3_MP3") (pintype "bidirectional"))
      (node (ref "_J2") (pin "MP4") (pinfunction "MP4_MP4") (pintype "bidirectional"))
      (node (ref "_J4") (pin "G1") (pinfunction "GND_1_G1") (pintype "bidirectional"))
      (node (ref "_J4") (pin "G2") (pinfunction "GND_2_G2") (pintype "bidirectional"))
      (node (ref "_J4") (pin "G3") (pinfunction "GND_3_G3") (pintype "bidirectional"))
      (node (ref "_J4") (pin "G4") (pinfunction "GND_4_G4") (pintype "bidirectional"))
      (node (ref "_J4") (pin "P6") (pinfunction "VSS_P6") (pintype "bidirectional"))
    )
    (net (code "14") (name "GPIO8") (class "Default")
      (node (ref "R1") (pin "2") (pinfunction "2_2") (pintype "passive"))
      (node (ref "U2") (pin "10") (pinfunction "IO8_10") (pintype "bidirectional"))
    )
    (net (code "15") (name "I2C_PW") (class "Default")
      (node (ref "C1") (pin "1") (pinfunction "1_1") (pintype "passive"))
      (node (ref "C2") (pin "1") (pinfunction "1_1") (pintype "passive"))
      (node (ref "R1-PINH") (pin "2") (pinfunction "2_2") (pintype "passive"))
      (node (ref "R2-PINH") (pin "2") (pinfunction "2_2") (pintype "passive"))
      (node (ref "SENSOR2") (pin "2") (pinfunction "CSB_2") (pintype "input"))
      (node (ref "SENSOR2") (pin "6") (pinfunction "VDDIO_6") (pintype "power_in"))
      (node (ref "SENSOR2") (pin "8") (pinfunction "VDD_8") (pintype "power_in"))
      (node (ref "U2") (pin "17") (pinfunction "IO19_17") (pintype "bidirectional"))
    )
    (net (code "16") (name "INT_RTC") (class "Default")
      (node (ref "INT_RTC") (pin "TP") (pinfunction "TP_TP") (pintype "input"))
      (node (ref "R1_PINH1") (pin "1") (pinfunction "1_1") (pintype "passive"))
      (node (ref "U2") (pin "8") (pinfunction "IO0_8") (pintype "bidirectional"))
      (node (ref "U3") (pin "3") (pinfunction "SQW/~{INT}_3") (pintype "output"))
    )
    (net (code "17") (name "IO{slash}BOOT") (class "Default")
      (node (ref "BOOT_BUTTON") (pin "3") (pinfunction "3_3") (pintype "passive"))
      (node (ref "BOOT_BUTTON") (pin "4") (pinfunction "4_4") (pintype "passive"))
      (node (ref "C6") (pin "1") (pinfunction "1_1") (pintype "passive"))
      (node (ref "R_BOOT") (pin "2") (pinfunction "2_2") (pintype "passive"))
      (node (ref "U2") (pin "15") (pinfunction "IO9_15") (pintype "bidirectional"))
    )
    (net (code "18") (name "IO{slash}CHANGE") (class "Default")
      (node (ref "C10") (pin "1") (pinfunction "1_1") (pintype "passive"))
      (node (ref "CHANGE_BUTTON") (pin "3") (pinfunction "3_3") (pintype "passive"))
      (node (ref "CHANGE_BUTTON") (pin "4") (pinfunction "4_4") (pintype "passive"))
      (node (ref "R_CHANGE") (pin "2") (pinfunction "2_2") (pintype "passive"))
      (node (ref "U2") (pin "23") (pinfunction "IO15_23") (pintype "bidirectional"))
    )
    (net (code "19") (name "MISO") (class "Default")
      (node (ref "MISO") (pin "TP") (pinfunction "TP_TP") (pintype "input"))
      (node (ref "R8") (pin "1") (pinfunction "1_1") (pintype "passive"))
      (node (ref "U1") (pin "2") (pinfunction "DO(IO1)_2") (pintype "bidirectional"))
      (node (ref "U2") (pin "27") (pinfunction "IO2_27") (pintype "bidirectional"))
      (node (ref "_D12") (pin "2") (pinfunction "2_2") (pintype "passive"))
      (node (ref "_J4") (pin "P7") (pinfunction "DAT0_P7") (pintype "bidirectional"))
    )
    (net (code "20") (name "MOSI") (class "Default")
      (node (ref "J1") (pin "14") (pinfunction "14_14") (pintype "bidirectional"))
      (node (ref "MOSI") (pin "TP") (pinfunction "TP_TP") (pintype "input"))
      (node (ref "R7") (pin "1") (pinfunction "1_1") (pintype "passive"))
      (node (ref "U1") (pin "5") (pinfunction "DI(IO0)_5") (pintype "bidirectional"))
      (node (ref "U2") (pin "7") (pinfunction "IO7_7") (pintype "bidirectional"))
      (node (ref "_D11") (pin "2") (pinfunction "2_2") (pintype "passive"))
    )
    (net (code "21") (name "Net-(C12-Pad1)") (class "Default")
      (node (ref "C12") (pin "1") (pinfunction "1_1") (pintype "passive"))
      (node (ref "J1") (pin "24") (pinfunction "24_24") (pintype "bidirectional"))
    )
    (net (code "22") (name "Net-(CHG_LED-PadC)") (class "Default")
      (node (ref "CHG_LED") (pin "C") (pinfunction "C_C") (pintype "passive"))
      (node (ref "R1_BAT") (pin "1") (pinfunction "1_1") (pintype "passive"))
    )
    (net (code "23") (name "Net-(D2-CATHODE)") (class "Default")
      (node (ref "C1_BAT1") (pin "1") (pinfunction "1_1") (pintype "passive"))
      (node (ref "D2") (pin "1") (pinfunction "CATHODE_1") (pintype "bidirectional"))
      (node (ref "IC4") (pin "1") (pinfunction "VIN_1") (pintype "bidirectional"))
      (node (ref "IC4") (pin "3") (pinfunction "CE_3") (pintype "bidirectional"))
      (node (ref "Q1") (pin "2") (pinfunction "S_2") (pintype "bidirectional"))
    )
    (net (code "24") (name "Net-(D3-A)") (class "Default")
      (node (ref "C4") (pin "1") (pinfunction "1_1") (pintype "passive"))
      (node (ref "D3") (pin "2") (pinfunction "A_2") (pintype "bidirectional"))
      (node (ref "D4") (pin "1") (pinfunction "K_1") (pintype "bidirectional"))
    )
    (net (code "25") (name "Net-(D7-CATHODE)") (class "Default")
      (node (ref "D7") (pin "1") (pinfunction "CATHODE_1") (pintype "bidirectional"))
      (node (ref "R_CAPACITOR") (pin "2") (pinfunction "2_2") (pintype "passive"))
    )
    (net (code "26") (name "Net-(EPD_C1-Pad1)") (class "Default")
      (node (ref "EPD_C1") (pin "1") (pinfunction "1_1") (pintype "passive"))
      (node (ref "J1") (pin "4") (pinfunction "4_4") (pintype "bidirectional"))
    )
    (net (code "27") (name "Net-(EPD_C2-Pad1)") (class "Default")
      (node (ref "EPD_C2") (pin "1") (pinfunction "1_1") (pintype "passive"))
      (node (ref "J1") (pin "5") (pinfunction "5_5") (pintype "bidirectional"))
    )
    (net (code "28") (name "Net-(EPD_C6-Pad1)") (class "Default")
      (node (ref "EPD_C6") (pin "1") (pinfunction "1_1") (pintype "passive"))
      (node (ref "J1") (pin "18") (pinfunction "18_18") (pintype "bidirectional"))
    )
    (net (code "29") (name "Net-(EPD_C7-Pad1)") (class "Default")
      (node (ref "EPD_C7") (pin "1") (pinfunction "1_1") (pintype "passive"))
      (node (ref "J1") (pin "19") (pinfunction "19_19") (pintype "bidirectional"))
    )
    (net (code "30") (name "Net-(EPD_C8-Pad1)") (class "Default")
      (node (ref "EPD_C8") (pin "1") (pinfunction "1_1") (pintype "passive"))
      (node (ref "J1") (pin "20") (pinfunction "20_20") (pintype "bidirectional"))
    )
    (net (code "31") (name "Net-(EPD_C10-Pad1)") (class "Default")
      (node (ref "EPD_C10") (pin "1") (pinfunction "1_1") (pintype "passive"))
      (node (ref "J1") (pin "22") (pinfunction "22_22") (pintype "bidirectional"))
    )
    (net (code "32") (name "Net-(IC2-CT)") (class "Default")
      (node (ref "C_DELAY") (pin "1") (pinfunction "1_1") (pintype "passive"))
      (node (ref "IC2") (pin "5") (pinfunction "CT_5") (pintype "bidirectional"))
    )
    (net (code "33") (name "Net-(MCP73831-PROG)") (class "Default")
      (node (ref "MCP73831") (pin "5") (pinfunction "PROG_5") (pintype "input"))
      (node (ref "R2_BAT") (pin "2") (pinfunction "2_2") (pintype "passive"))
    )
    (net (code "34") (name "Net-(MCP73831-STAT)") (class "Default")
      (node (ref "MCP73831") (pin "1") (pinfunction "STAT_1") (pintype "output"))
      (node (ref "R1_BAT") (pin "2") (pinfunction "2_2") (pintype "passive"))
    )
    (net (code "35") (name "Net-(R2-USB-Pad1)") (class "Default")
      (node (ref "R2-USB") (pin "1") (pinfunction "1_1") (pintype "passive"))
      (node (ref "_J2") (pin "B5") (pinfunction "B5_B5") (pintype "bidirectional"))
    )
    (net (code "36") (name "Net-(R2-USB1-Pad2)") (class "Default")
      (node (ref "R2-USB1") (pin "2") (pinfunction "2_2") (pintype "passive"))
      (node (ref "_J2") (pin "A5") (pinfunction "A5_A5") (pintype "bidirectional"))
    )
    (net (code "37") (name "PREVGH") (class "Default")
      (node (ref "D5") (pin "1") (pinfunction "K_1") (pintype "bidirectional"))
      (node (ref "EPD_C9") (pin "1") (pinfunction "1_1") (pintype "passive"))
      (node (ref "J1") (pin "21") (pinfunction "21_21") (pintype "bidirectional"))
    )
    (net (code "38") (name "PREVGL") (class "Default")
      (node (ref "C11") (pin "1") (pinfunction "1_1") (pintype "passive"))
      (node (ref "D4") (pin "2") (pinfunction "A_2") (pintype "bidirectional"))
      (node (ref "J1") (pin "23") (pinfunction "23_23") (pintype "bidirectional"))
    )
    (net (code "39") (name "RESE") (class "Default")
      (node (ref "J1") (pin "3") (pinfunction "3_3") (pintype "bidirectional"))
      (node (ref "R3") (pin "1") (pinfunction "1_1") (pintype "passive"))
      (node (ref "_Q3") (pin "2") (pinfunction "S_2") (pintype "bidirectional"))
    )
    (net (code "40") (name "RESE'") (class "Default")
      (node (ref "R2") (pin "2") (pinfunction "2_2") (pintype "passive"))
      (node (ref "R3") (pin "2") (pinfunction "2_2") (pintype "passive"))
      (node (ref "SJ1") (pin "2") (pinfunction "2_2") (pintype "passive"))
    )
    (net (code "41") (name "RESET") (class "Default")
      (node (ref "C5") (pin "1") (pinfunction "1_1") (pintype "passive"))
      (node (ref "IC2") (pin "1") (pinfunction "VOUT_1") (pintype "bidirectional"))
      (node (ref "RESET_BUTTON") (pin "3") (pinfunction "3_3") (pintype "passive"))
      (node (ref "RESET_BUTTON") (pin "4") (pinfunction "4_4") (pintype "passive"))
      (node (ref "R_RESET") (pin "2") (pinfunction "2_2") (pintype "passive"))
      (node (ref "U2") (pin "3") (pinfunction "EN_3") (pintype "input"))
    )
    (net (code "42") (name "RTC_RST") (class "Default")
      (node (ref "U2") (pin "16") (pinfunction "IO18_16") (pintype "bidirectional"))
      (node (ref "U3") (pin "4") (pinfunction "~{RST}_4") (pintype "input"))
    )
    (net (code "43") (name "RX") (class "Default")
      (node (ref "RX") (pin "TP") (pinfunction "TP_TP") (pintype "input"))
      (node (ref "U2") (pin "24") (pinfunction "RXD0/GPIO17_24") (pintype "bidirectional"))
    )
    (net (code "44") (name "SCK") (class "Default")
      (node (ref "J1") (pin "13") (pinfunction "13_13") (pintype "bidirectional"))
      (node (ref "R6") (pin "1") (pinfunction "1_1") (pintype "passive"))
      (node (ref "SCK") (pin "TP") (pinfunction "TP_TP") (pintype "input"))
      (node (ref "U1") (pin "6") (pinfunction "CLK_6") (pintype "input"))
      (node (ref "U2") (pin "6") (pinfunction "IO6_6") (pintype "bidirectional"))
      (node (ref "_D10") (pin "2") (pinfunction "2_2") (pintype "passive"))
      (node (ref "_J4") (pin "P5") (pinfunction "CLK_P5") (pintype "bidirectional"))
    )
    (net (code "45") (name "SCL") (class "Default")
      (node (ref "J4") (pin "4") (pinfunction "4_4") (pintype "passive"))
      (node (ref "R2-PINH") (pin "1") (pinfunction "1_1") (pintype "passive"))
      (node (ref "SENSOR2") (pin "4") (pinfunction "SCK_4") (pintype "input"))
      (node (ref "U2") (pin "20") (pinfunction "IO22_20") (pintype "bidirectional"))
      (node (ref "U3") (pin "16") (pinfunction "SCL_16") (pintype "input"))
      (node (ref "U4") (pin "7") (pinfunction "SCL_7") (pintype "input"))
    )
    (net (code "46") (name "SDA") (class "Default")
      (node (ref "J4") (pin "3") (pinfunction "3_3") (pintype "passive"))
      (node (ref "R1-PINH") (pin "1") (pinfunction "1_1") (pintype "passive"))
      (node (ref "SENSOR2") (pin "3") (pinfunction "SDI_3") (pintype "bidirectional"))
      (node (ref "U2") (pin "19") (pinfunction "IO21_19") (pintype "bidirectional"))
      (node (ref "U3") (pin "15") (pinfunction "SDA_15") (pintype "bidirectional"))
      (node (ref "U4") (pin "8") (pinfunction "SDA_8") (pintype "bidirectional"))
    )
    (net (code "47") (name "SRC") (class "Default")
      (node (ref "C4") (pin "2") (pinfunction "2_2") (pintype "passive"))
      (node (ref "D5") (pin "2") (pinfunction "A_2") (pintype "bidirectional"))
      (node (ref "L1") (pin "1") (pinfunction "1_1") (pintype "passive"))
      (node (ref "_Q3") (pin "3") (pinfunction "D_3") (pintype "bidirectional"))
    )
    (net (code "48") (name "SS_SD") (class "Default")
      (node (ref "R10") (pin "1") (pinfunction "1_1") (pintype "passive"))
      (node (ref "U2") (pin "4") (pinfunction "IO4_4") (pintype "bidirectional"))
      (node (ref "_D8") (pin "2") (pinfunction "2_2") (pintype "passive"))
    )
    (net (code "49") (name "TX") (class "Default")
      (node (ref "TX") (pin "TP") (pinfunction "TP_TP") (pintype "input"))
      (node (ref "U2") (pin "25") (pinfunction "TXD0/GPIO16_25") (pintype "bidirectional"))
    )
    (net (code "50") (name "USB_D+") (class "Default")
      (node (ref "D1") (pin "1") (pinfunction "I/O1_1_1") (pintype "bidirectional"))
      (node (ref "U2") (pin "14") (pinfunction "IO13_14") (pintype "bidirectional"))
    )
    (net (code "51") (name "USB_D-") (class "Default")
      (node (ref "D1") (pin "3") (pinfunction "I/O2_1_3") (pintype "bidirectional"))
      (node (ref "U2") (pin "13") (pinfunction "IO12_13") (pintype "bidirectional"))
    )
    (net (code "52") (name "VBAT") (class "Default")
      (node (ref "C2_BAT") (pin "1") (pinfunction "1_1") (pintype "passive"))
      (node (ref "MCP73831") (pin "3") (pinfunction "VBAT_3") (pintype "power_in"))
      (node (ref "Q1") (pin "3") (pinfunction "D_3") (pintype "bidirectional"))
      (node (ref "U4") (pin "2") (pinfunction "CELL_2") (pintype "power_in"))
      (node (ref "U4") (pin "3") (pinfunction "VDD_3") (pintype "power_in"))
      (node (ref "VBAT") (pin "TP") (pinfunction "TP_TP") (pintype "input"))
    )
    (net (code "53") (name "VBUS") (class "Default")
      (node (ref "C1_BAT") (pin "1") (pinfunction "1_1") (pintype "passive"))
      (node (ref "C4_USB") (pin "1") (pinfunction "1_1") (pintype "passive"))
      (node (ref "C5_USB") (pin "1") (pinfunction "1_1") (pintype "passive"))
      (node (ref "CHG_LED") (pin "A") (pinfunction "A_A") (pintype "passive"))
      (node (ref "D1") (pin "5") (pinfunction "VBUS_5") (pintype "bidirectional"))
      (node (ref "D2") (pin "2") (pinfunction "ANODE_2") (pintype "bidirectional"))
      (node (ref "MCP73831") (pin "4") (pinfunction "VIN_4") (pintype "power_in"))
      (node (ref "PFMF.050.1") (pin "2") (pinfunction "2_2") (pintype "passive"))
      (node (ref "Q1") (pin "1") (pinfunction "G_1") (pintype "bidirectional"))
      (node (ref "R1_PWRUSB") (pin "2") (pinfunction "2_2") (pintype "passive"))
      (node (ref "VBUS") (pin "TP") (pinfunction "TP_TP") (pintype "input"))
    )
    (net (code "54") (name "VRTC") (class "Default")
      (node (ref "C10_SUPERCAP") (pin "2") (pinfunction "2_2") (pintype "passive"))
      (node (ref "C8") (pin "1") (pinfunction "1_1") (pintype "passive"))
      (node (ref "R_CAPACITOR") (pin "1") (pinfunction "1_1") (pintype "passive"))
      (node (ref "U3") (pin "14") (pinfunction "VBAT_14") (pintype "power_in"))
    )
    (net (code "55") (name "VUSB") (class "Default")
      (node (ref "PFMF.050.1") (pin "1") (pinfunction "1_1") (pintype "passive"))
      (node (ref "_J2") (pin "A4") (pinfunction "A4_A4") (pintype "bidirectional"))
      (node (ref "_J2") (pin "A9") (pinfunction "A9_A9") (pintype "bidirectional"))
      (node (ref "_J2") (pin "B4") (pinfunction "B4_B4") (pintype "bidirectional"))
      (node (ref "_J2") (pin "B9") (pinfunction "B9_B9") (pintype "bidirectional"))
    )
    (net (code "56") (name "unconnected-(IC2-NC-Pad4)") (class "Default")
      (node (ref "IC2") (pin "4") (pinfunction "NC_4") (pintype "no_connect"))
    )
    (net (code "57") (name "unconnected-(IC4-NC-Pad4)") (class "Default")
      (node (ref "IC4") (pin "4") (pinfunction "NC_4") (pintype "no_connect"))
    )
    (net (code "58") (name "unconnected-(J1-Pad1)") (class "Default")
      (node (ref "J1") (pin "1") (pinfunction "1_1") (pintype "bidirectional"))
    )
    (net (code "59") (name "unconnected-(J1-Pad6)") (class "Default")
      (node (ref "J1") (pin "6") (pinfunction "6_6") (pintype "bidirectional"))
    )
    (net (code "60") (name "unconnected-(J1-Pad7)") (class "Default")
      (node (ref "J1") (pin "7") (pinfunction "7_7") (pintype "bidirectional"))
    )
    (net (code "61") (name "unconnected-(U2-NC-Pad22)") (class "Default")
      (node (ref "U2") (pin "22") (pinfunction "NC_22") (pintype "no_connect"))
    )
    (net (code "62") (name "unconnected-(U4-~{ALERT}-Pad5)") (class "Default")
      (node (ref "U4") (pin "5") (pinfunction "~{ALERT}_5") (pintype "output"))
    )
    (net (code "63") (name "unconnected-(_J2-PadA8)") (class "Default")
      (node (ref "_J2") (pin "A8") (pinfunction "A8_A8") (pintype "bidirectional"))
    )
    (net (code "64") (name "unconnected-(_J2-PadB8)") (class "Default")
      (node (ref "_J2") (pin "B8") (pinfunction "B8_B8") (pintype "bidirectional"))
    )
    (net (code "65") (name "unconnected-(_J4-CD{slash}DAT3-PadP2)") (class "Default")
      (node (ref "_J4") (pin "P2") (pinfunction "CD/DAT3_P2") (pintype "bidirectional"))
    )
    (net (code "66") (name "unconnected-(_J4-CMD-PadP3)") (class "Default")
      (node (ref "_J4") (pin "P3") (pinfunction "CMD_P3") (pintype "bidirectional"))
    )
    (net (code "67") (name "unconnected-(_J4-DAT1-PadP8)") (class "Default")
      (node (ref "_J4") (pin "P8") (pinfunction "DAT1_P8") (pintype "bidirectional"))
    )
    (net (code "68") (name "unconnected-(_J4-DAT2-PadP1)") (class "Default")
      (node (ref "_J4") (pin "P1") (pinfunction "DAT2_P1") (pintype "bidirectional"))
    )
    (net (code "69") (name "unconnected-(_J4-DETECTION_1-PadS1)") (class "Default")
      (node (ref "_J4") (pin "S1") (pinfunction "DETECTION_1_S1") (pintype "bidirectional"))
    )
    (net (code "70") (name "unconnected-(_J4-DETECTION_2-PadS2)") (class "Default")
      (node (ref "_J4") (pin "S2") (pinfunction "DETECTION_2_S2") (pintype "bidirectional"))
    )
  )
)
